# Connectors.net
KiCad netlist of a schematic drawn in Altium Designer
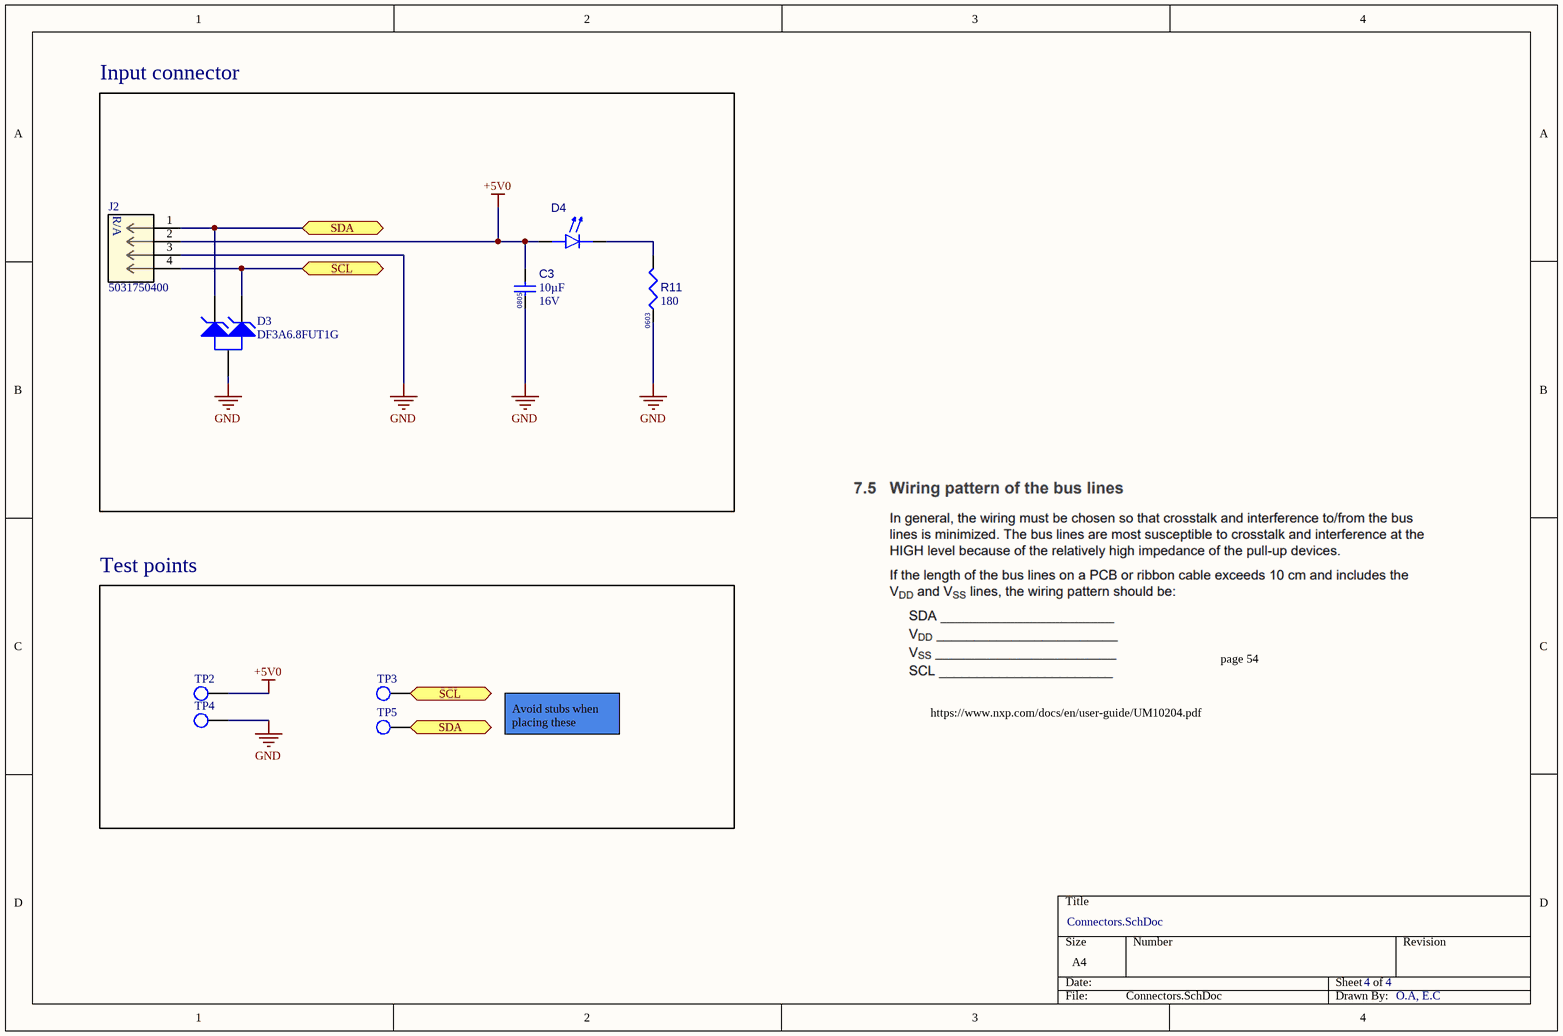
[diagram p0: Connectors.SchDoc]

(export (version "E")
  (design (tool "Eeschema 10.0.6"))
  (components
    (comp (ref "C3")
      (value "10µF")
      (footprint "CAP CER 10UF 16V X5R 0805-Footprint-1")
      (fields
        (field (name "VOLTAGE RATING") "16V")
        (field (name "CASE/PACKAGE") "0805")
        (field (name "Comment") "CAP CER 10UF 16V X5R 0805")
      )
      (libsource (lib "hawaiirobotics") (part "CAP-NP-2"))
    )
    (comp (ref "D3")
      (value "DF3A6.8FUT1G")
      (footprint "ONSC-SC-70-3-419-04_V")
      (description "Trans Voltage Suppressor Diode, 150W, Unidirectional, 2 Element, Silicon")
      (libsource (lib "hawaiirobotics") (part "ONSC-K1K2A3-3"))
    )
    (comp (ref "D4")
      (value "150060RS75000")
      (footprint "WL-SMCW_0603_150060xx75000")
      (description "Single Color LED, Red, Water Clear, 1.1mm")
      (libsource (lib "hawaiirobotics") (part "DIODE-LED-2"))
    )
    (comp (ref "J2")
      (value "5031750400")
      (footprint "5031750400-Footprint-1")
      (libsource (lib "hawaiirobotics") (part "5031750400-Symbol-1"))
    )
    (comp (ref "R11")
      (value "180")
      (footprint "RESC0603(1608)_N")
      (fields
        (field (name "TOLERANCE") "5%")
        (field (name "CASE/PACKAGE") "0603")
        (field (name "POWER") "100mW")
        (field (name "Comment") "RC0603JR-07180RL")
      )
      (libsource (lib "hawaiirobotics") (part "RES-2"))
    )
    (comp (ref "TP2")
      (value "RCUCTE")
      (footprint "FP-S2761-46R-MFG")
      (description "Test point")
      (libsource (lib "hawaiirobotics") (part "RCUCTE-Symbol-1"))
    )
    (comp (ref "TP3")
      (value "RCUCTE")
      (footprint "FP-S2761-46R-MFG")
      (description "Test point")
      (libsource (lib "hawaiirobotics") (part "RCUCTE-Symbol-1"))
    )
    (comp (ref "TP4")
      (value "RCUCTE")
      (footprint "FP-S2761-46R-MFG")
      (description "Test point")
      (libsource (lib "hawaiirobotics") (part "RCUCTE-Symbol-1"))
    )
    (comp (ref "TP5")
      (value "RCUCTE")
      (footprint "FP-S2761-46R-MFG")
      (description "Test point")
      (libsource (lib "hawaiirobotics") (part "RCUCTE-Symbol-1"))
    )
  )
  (nets
    (net (code "1") (name "+5V0") (class "Default")
      (node (ref "C3") (pin "2") (pinfunction "2_2") (pintype "passive"))
      (node (ref "D4") (pin "2") (pinfunction "A_2") (pintype "passive"))
      (node (ref "J2") (pin "2") (pinfunction "2_2") (pintype "passive"))
      (node (ref "TP2") (pin "1") (pinfunction "1_1") (pintype "passive"))
    )
    (net (code "2") (name "/SCL") (class "Default")
      (node (ref "D3") (pin "2") (pinfunction "K2_2") (pintype "passive"))
      (node (ref "J2") (pin "4") (pinfunction "4_4") (pintype "passive"))
      (node (ref "TP3") (pin "1") (pinfunction "1_1") (pintype "passive"))
    )
    (net (code "3") (name "/SDA") (class "Default")
      (node (ref "D3") (pin "1") (pinfunction "K1_1") (pintype "passive"))
      (node (ref "J2") (pin "1") (pinfunction "1_1") (pintype "passive"))
      (node (ref "TP5") (pin "1") (pinfunction "1_1") (pintype "passive"))
    )
    (net (code "4") (name "GND") (class "Default")
      (node (ref "C3") (pin "1") (pinfunction "1_1") (pintype "passive"))
      (node (ref "D3") (pin "3") (pinfunction "A_3") (pintype "passive"))
      (node (ref "J2") (pin "3") (pinfunction "3_3") (pintype "passive"))
      (node (ref "R11") (pin "1") (pinfunction "1_1") (pintype "passive"))
      (node (ref "TP4") (pin "1") (pinfunction "1_1") (pintype "passive"))
    )
    (net (code "5") (name "Net-(D4-K)") (class "Default")
      (node (ref "D4") (pin "1") (pinfunction "K_1") (pintype "passive"))
      (node (ref "R11") (pin "2") (pinfunction "2_2") (pintype "passive"))
    )
  )
)
